# MBC3_multi_1-3.net
KiCad netlist of a schematic drawn in EAGLE
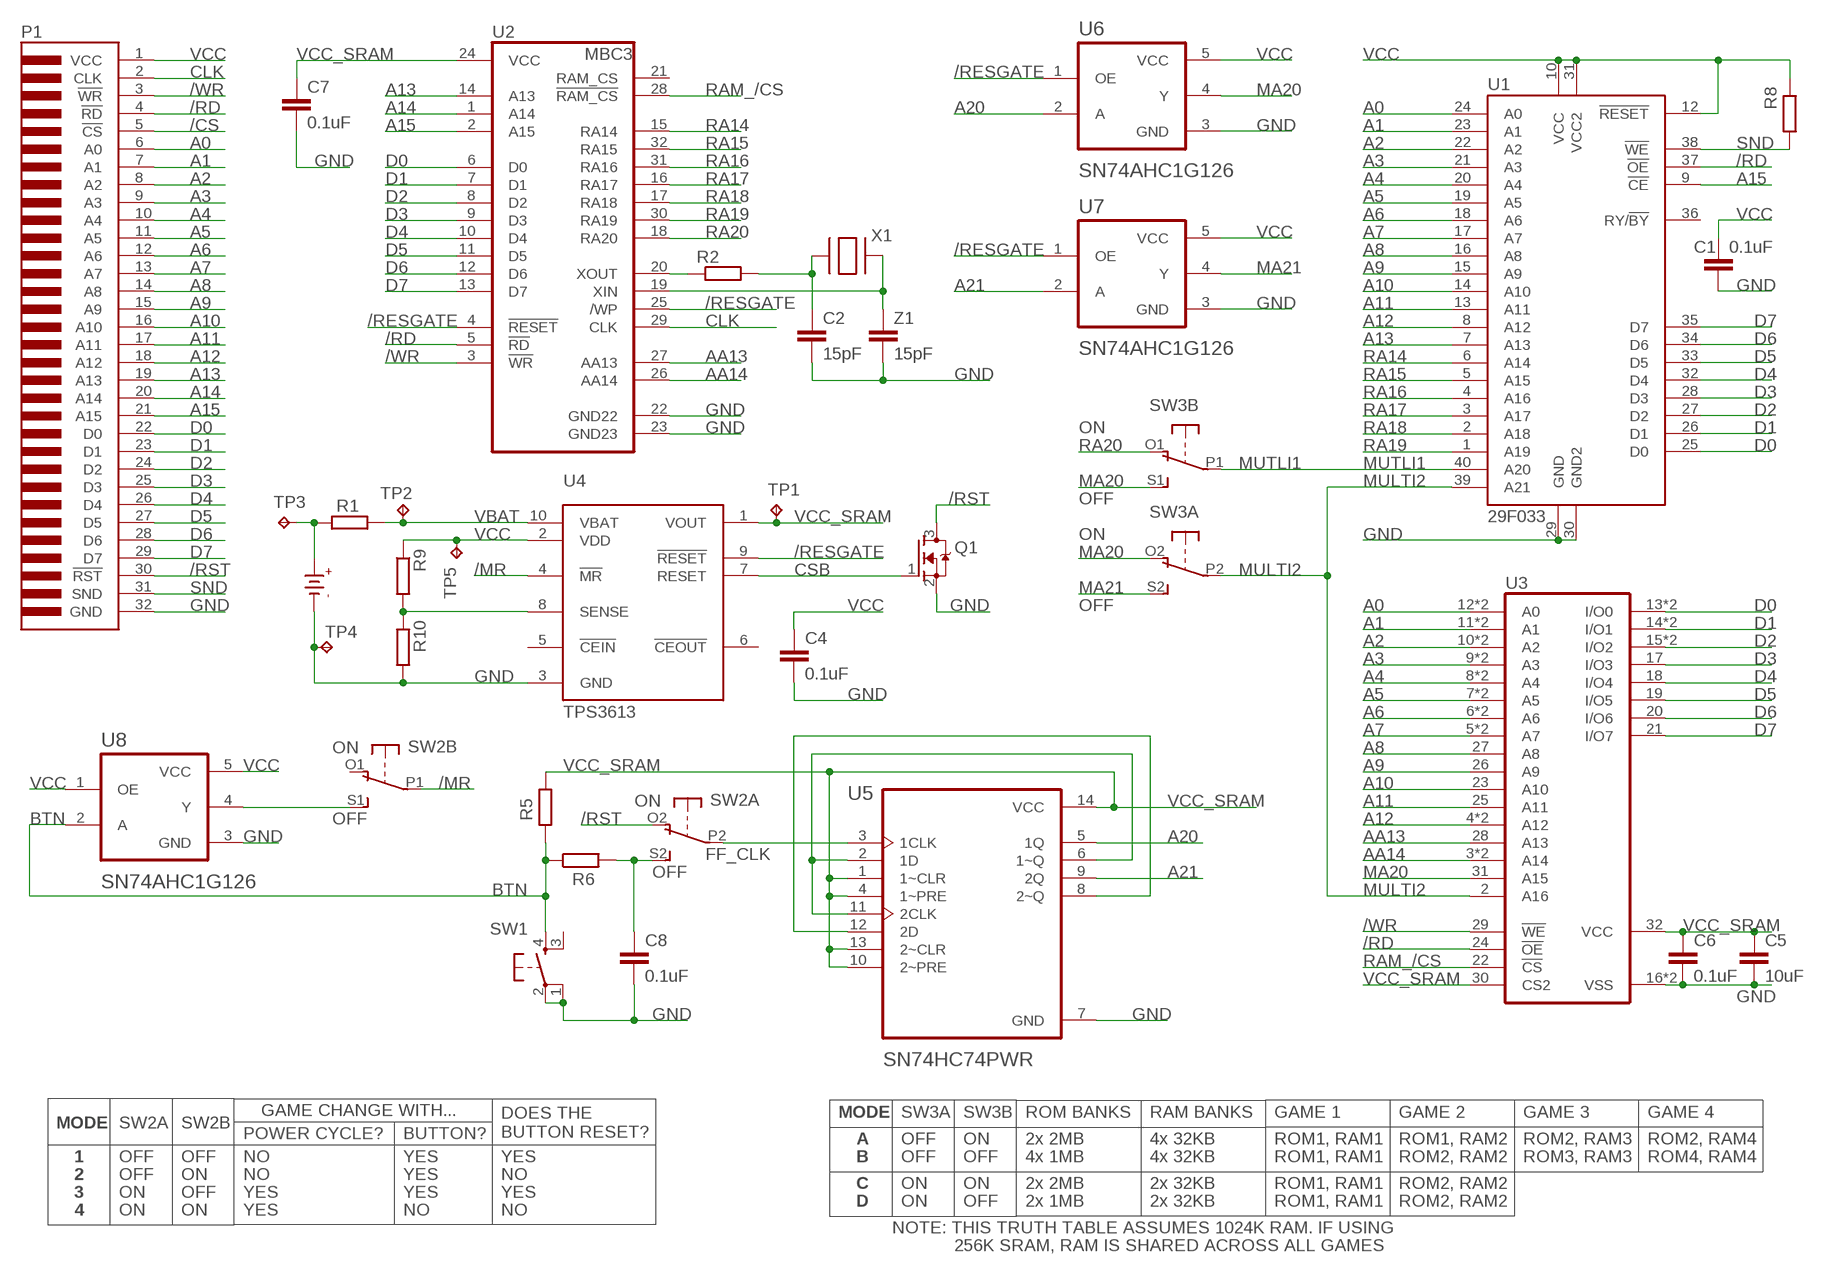
[diagram p0: schematic, sheet 1]

(export (version "E")
  (design (tool "Eeschema 10.0.6"))
  (components
    (comp (ref "C1")
      (value "0.1uF")
      (footprint "eagle-import:C0603")
      (libsource (lib "eagle-import") (part "C-EUC0603"))
    )
    (comp (ref "C2")
      (value "15pF")
      (footprint "eagle-import:C0603")
      (libsource (lib "eagle-import") (part "C-EUC0603"))
    )
    (comp (ref "C4")
      (value "0.1uF")
      (footprint "eagle-import:C0603")
      (libsource (lib "eagle-import") (part "C-EUC0603"))
    )
    (comp (ref "C5")
      (value "10uF")
      (footprint "eagle-import:C0603")
      (libsource (lib "eagle-import") (part "C-EUC0603"))
    )
    (comp (ref "C6")
      (value "0.1uF")
      (footprint "eagle-import:C0603")
      (libsource (lib "eagle-import") (part "C-EUC0603"))
    )
    (comp (ref "C7")
      (value "0.1uF")
      (footprint "eagle-import:C0603")
      (libsource (lib "eagle-import") (part "C-EUC0603"))
    )
    (comp (ref "C8")
      (value "0.1uF")
      (footprint "eagle-import:C0603")
      (libsource (lib "eagle-import") (part "C-EUC0603"))
    )
    (comp (ref "P1")
      (value "GBC_CARTTAB")
      (footprint "eagle-import:GBC_CART_TABBED")
      (libsource (lib "eagle-import") (part "GBC_CARTTAB"))
    )
    (comp (ref "Q1")
      (value "2N7002")
      (footprint "eagle-import:SOT23")
      (libsource (lib "eagle-import") (part "MOSFET-NREFLOW"))
    )
    (comp (ref "R1")
      (value "RR0603")
      (footprint "eagle-import:R0603")
      (libsource (lib "eagle-import") (part "RR0603"))
    )
    (comp (ref "R2")
      (value "RR0603")
      (footprint "eagle-import:R0603")
      (libsource (lib "eagle-import") (part "RR0603"))
    )
    (comp (ref "R5")
      (value "RR0603")
      (footprint "eagle-import:R0603")
      (libsource (lib "eagle-import") (part "RR0603"))
    )
    (comp (ref "R6")
      (value "RR0603")
      (footprint "eagle-import:R0603")
      (libsource (lib "eagle-import") (part "RR0603"))
    )
    (comp (ref "R8")
      (value "RR0603")
      (footprint "eagle-import:R0603")
      (libsource (lib "eagle-import") (part "RR0603"))
    )
    (comp (ref "R9")
      (value "RR0603")
      (footprint "eagle-import:R0603")
      (libsource (lib "eagle-import") (part "RR0603"))
    )
    (comp (ref "R10")
      (value "RR0603")
      (footprint "eagle-import:R0603")
      (libsource (lib "eagle-import") (part "RR0603"))
    )
    (comp (ref "SW1")
      (value "SPST_TACT-KMR2")
      (footprint "eagle-import:KMR2")
      (libsource (lib "eagle-import") (part "SPST_TACT-KMR2"))
    )
    (comp (ref "SW2")
      (value "SPDT-2S")
      (footprint "eagle-import:CAS-D20A")
      (libsource (lib "eagle-import") (part "SPDT-2S"))
    )
    (comp (ref "SW3")
      (value "SPDT-2S")
      (footprint "eagle-import:CAS-D20A")
      (libsource (lib "eagle-import") (part "SPDT-2S"))
    )
    (comp (ref "TP1")
      (value "TPB1,27")
      (footprint "eagle-import:B1,27")
      (libsource (lib "eagle-import") (part "TPB1,27"))
    )
    (comp (ref "TP2")
      (value "TPB1,27")
      (footprint "eagle-import:B1,27")
      (libsource (lib "eagle-import") (part "TPB1,27"))
    )
    (comp (ref "TP3")
      (value "TPB1,27")
      (footprint "eagle-import:B1,27")
      (libsource (lib "eagle-import") (part "TPB1,27"))
    )
    (comp (ref "TP4")
      (value "TPB1,27")
      (footprint "eagle-import:B1,27")
      (libsource (lib "eagle-import") (part "TPB1,27"))
    )
    (comp (ref "TP5")
      (value "TPB1,27")
      (footprint "eagle-import:B1,27")
      (libsource (lib "eagle-import") (part "TPB1,27"))
    )
    (comp (ref "U$7")
      (value "CR2025")
      (footprint "eagle-import:CR2025")
      (libsource (lib "eagle-import") (part "CR2025"))
    )
    (comp (ref "U1")
      (value "29F033")
      (footprint "eagle-import:TSOP-40")
      (libsource (lib "eagle-import") (part "29F033"))
    )
    (comp (ref "U2")
      (value "MBC3")
      (footprint "eagle-import:QFP-32")
      (libsource (lib "eagle-import") (part "MBC3"))
    )
    (comp (ref "U3")
      (value "1008_62256_SRAM")
      (footprint "eagle-import:SOP-32L")
      (libsource (lib "eagle-import") (part "1008_62256_SRAM"))
    )
    (comp (ref "U4")
      (value "TPS3613")
      (footprint "eagle-import:MSOP-10")
      (libsource (lib "eagle-import") (part "TPS3613"))
    )
    (comp (ref "U5")
      (value "SN74HC74PWR")
      (footprint "eagle-import:SOP65P640X120-14N")
      (fields (field (name "MF") "Texas Instruments"))
      (libsource (lib "eagle-import") (part "SN74HC74PWR"))
    )
    (comp (ref "U6")
      (value "SN74AHC1G126")
      (footprint "eagle-import:SC70")
      (libsource (lib "eagle-import") (part "SN74AHC1G126"))
    )
    (comp (ref "U7")
      (value "SN74AHC1G126")
      (footprint "eagle-import:SC70")
      (libsource (lib "eagle-import") (part "SN74AHC1G126"))
    )
    (comp (ref "U8")
      (value "SN74AHC1G126")
      (footprint "eagle-import:SC70")
      (libsource (lib "eagle-import") (part "SN74AHC1G126"))
    )
    (comp (ref "X1")
      (value "XTAL-3.2X1.5")
      (footprint "eagle-import:XTAL3215")
      (libsource (lib "eagle-import") (part "XTAL-3.2X1.5"))
    )
    (comp (ref "Z1")
      (value "15pF")
      (footprint "eagle-import:C0603")
      (libsource (lib "eagle-import") (part "C-EUC0603"))
    )
  )
  (nets
    (net (code "1") (name "/A0") (class "Default")
      (node (ref "P1") (pin "6") (pinfunction "A0_6") (pintype "output"))
      (node (ref "U1") (pin "24") (pinfunction "A0_24") (pintype "input"))
      (node (ref "U3") (pin "12") (pinfunction "A0_12") (pintype "input"))
      (node (ref "U3") (pin "L12") (pinfunction "A0_L12") (pintype "input"))
    )
    (net (code "2") (name "/A1") (class "Default")
      (node (ref "P1") (pin "7") (pinfunction "A1_7") (pintype "output"))
      (node (ref "U1") (pin "23") (pinfunction "A1_23") (pintype "input"))
      (node (ref "U3") (pin "11") (pinfunction "A1_11") (pintype "input"))
      (node (ref "U3") (pin "L11") (pinfunction "A1_L11") (pintype "input"))
    )
    (net (code "3") (name "/A2") (class "Default")
      (node (ref "P1") (pin "8") (pinfunction "A2_8") (pintype "output"))
      (node (ref "U1") (pin "22") (pinfunction "A2_22") (pintype "input"))
      (node (ref "U3") (pin "10") (pinfunction "A2_10") (pintype "input"))
      (node (ref "U3") (pin "L10") (pinfunction "A2_L10") (pintype "input"))
    )
    (net (code "4") (name "/A3") (class "Default")
      (node (ref "P1") (pin "9") (pinfunction "A3_9") (pintype "output"))
      (node (ref "U1") (pin "21") (pinfunction "A3_21") (pintype "input"))
      (node (ref "U3") (pin "9") (pinfunction "A3_9") (pintype "input"))
      (node (ref "U3") (pin "L9") (pinfunction "A3_L9") (pintype "input"))
    )
    (net (code "5") (name "/A4") (class "Default")
      (node (ref "P1") (pin "10") (pinfunction "A4_10") (pintype "output"))
      (node (ref "U1") (pin "20") (pinfunction "A4_20") (pintype "input"))
      (node (ref "U3") (pin "8") (pinfunction "A4_8") (pintype "input"))
      (node (ref "U3") (pin "L8") (pinfunction "A4_L8") (pintype "input"))
    )
    (net (code "6") (name "/A5") (class "Default")
      (node (ref "P1") (pin "11") (pinfunction "A5_11") (pintype "output"))
      (node (ref "U1") (pin "19") (pinfunction "A5_19") (pintype "input"))
      (node (ref "U3") (pin "7") (pinfunction "A5_7") (pintype "input"))
      (node (ref "U3") (pin "L7") (pinfunction "A5_L7") (pintype "input"))
    )
    (net (code "7") (name "/A6") (class "Default")
      (node (ref "P1") (pin "12") (pinfunction "A6_12") (pintype "output"))
      (node (ref "U1") (pin "18") (pinfunction "A6_18") (pintype "input"))
      (node (ref "U3") (pin "6") (pinfunction "A6_6") (pintype "input"))
      (node (ref "U3") (pin "L6") (pinfunction "A6_L6") (pintype "input"))
    )
    (net (code "8") (name "/A7") (class "Default")
      (node (ref "P1") (pin "13") (pinfunction "A7_13") (pintype "output"))
      (node (ref "U1") (pin "17") (pinfunction "A7_17") (pintype "input"))
      (node (ref "U3") (pin "5") (pinfunction "A7_5") (pintype "input"))
      (node (ref "U3") (pin "L5") (pinfunction "A7_L5") (pintype "input"))
    )
    (net (code "9") (name "/A8") (class "Default")
      (node (ref "P1") (pin "14") (pinfunction "A8_14") (pintype "output"))
      (node (ref "U1") (pin "16") (pinfunction "A8_16") (pintype "input"))
      (node (ref "U3") (pin "27") (pinfunction "A8_27") (pintype "input"))
    )
    (net (code "10") (name "/A9") (class "Default")
      (node (ref "P1") (pin "15") (pinfunction "A9_15") (pintype "output"))
      (node (ref "U1") (pin "15") (pinfunction "A9_15") (pintype "input"))
      (node (ref "U3") (pin "26") (pinfunction "A9_26") (pintype "input"))
    )
    (net (code "11") (name "/A10") (class "Default")
      (node (ref "P1") (pin "16") (pinfunction "A10_16") (pintype "output"))
      (node (ref "U1") (pin "14") (pinfunction "A10_14") (pintype "input"))
      (node (ref "U3") (pin "23") (pinfunction "A10_23") (pintype "input"))
    )
    (net (code "12") (name "/A11") (class "Default")
      (node (ref "P1") (pin "17") (pinfunction "A11_17") (pintype "output"))
      (node (ref "U1") (pin "13") (pinfunction "A11_13") (pintype "input"))
      (node (ref "U3") (pin "25") (pinfunction "A11_25") (pintype "input"))
    )
    (net (code "13") (name "/A12") (class "Default")
      (node (ref "P1") (pin "18") (pinfunction "A12_18") (pintype "output"))
      (node (ref "U1") (pin "8") (pinfunction "A12_8") (pintype "input"))
      (node (ref "U3") (pin "4") (pinfunction "A12_4") (pintype "input"))
      (node (ref "U3") (pin "L4") (pinfunction "A12_L4") (pintype "input"))
    )
    (net (code "14") (name "/A13") (class "Default")
      (node (ref "P1") (pin "19") (pinfunction "A13_19") (pintype "output"))
      (node (ref "U1") (pin "7") (pinfunction "A13_7") (pintype "input"))
      (node (ref "U2") (pin "14") (pinfunction "A13_14") (pintype "input"))
    )
    (net (code "15") (name "/A14") (class "Default")
      (node (ref "P1") (pin "20") (pinfunction "A14_20") (pintype "output"))
      (node (ref "U2") (pin "1") (pinfunction "A14_1") (pintype "input"))
    )
    (net (code "16") (name "/A15") (class "Default")
      (node (ref "P1") (pin "21") (pinfunction "A15_21") (pintype "output"))
      (node (ref "U1") (pin "9") (pinfunction "~{CE}_9") (pintype "input"))
      (node (ref "U2") (pin "2") (pinfunction "A15_2") (pintype "input"))
    )
    (net (code "17") (name "/A20") (class "Default")
      (node (ref "U5") (pin "5") (pinfunction "1Q_5") (pintype "output"))
      (node (ref "U6") (pin "2") (pinfunction "A_2") (pintype "input"))
    )
    (net (code "18") (name "/A21") (class "Default")
      (node (ref "U5") (pin "9") (pinfunction "2Q_9") (pintype "output"))
      (node (ref "U7") (pin "2") (pinfunction "A_2") (pintype "input"))
    )
    (net (code "19") (name "/AA13") (class "Default")
      (node (ref "U2") (pin "27") (pinfunction "AA13_27") (pintype "output"))
      (node (ref "U3") (pin "28") (pinfunction "A13_28") (pintype "input"))
    )
    (net (code "20") (name "/AA14") (class "Default")
      (node (ref "U2") (pin "26") (pinfunction "AA14_26") (pintype "output"))
      (node (ref "U3") (pin "3") (pinfunction "A14_3") (pintype "input"))
      (node (ref "U3") (pin "L3") (pinfunction "A14_L3") (pintype "input"))
    )
    (net (code "21") (name "/BTN") (class "Default")
      (node (ref "R5") (pin "2") (pinfunction "2_2") (pintype "passive"))
      (node (ref "R6") (pin "1") (pinfunction "1_1") (pintype "passive"))
      (node (ref "SW1") (pin "4") (pinfunction "S_4") (pintype "passive"))
      (node (ref "U8") (pin "2") (pinfunction "A_2") (pintype "input"))
    )
    (net (code "22") (name "/CLK") (class "Default")
      (node (ref "P1") (pin "2") (pinfunction "CLK_2") (pintype "output"))
      (node (ref "U2") (pin "29") (pinfunction "CLK_29") (pintype "output"))
    )
    (net (code "23") (name "/CSB") (class "Default")
      (node (ref "Q1") (pin "1") (pinfunction "G_1") (pintype "bidirectional"))
      (node (ref "U4") (pin "7") (pinfunction "RESET_7") (pintype "output"))
    )
    (net (code "24") (name "/D0") (class "Default")
      (node (ref "P1") (pin "22") (pinfunction "D0_22") (pintype "bidirectional"))
      (node (ref "U1") (pin "25") (pinfunction "D0_25") (pintype "bidirectional"))
      (node (ref "U2") (pin "6") (pinfunction "D0_6") (pintype "input"))
      (node (ref "U3") (pin "13") (pinfunction "I/O0_13") (pintype "bidirectional"))
      (node (ref "U3") (pin "L13") (pinfunction "I/O0_L13") (pintype "bidirectional"))
    )
    (net (code "25") (name "/D1") (class "Default")
      (node (ref "P1") (pin "23") (pinfunction "D1_23") (pintype "bidirectional"))
      (node (ref "U1") (pin "26") (pinfunction "D1_26") (pintype "bidirectional"))
      (node (ref "U2") (pin "7") (pinfunction "D1_7") (pintype "input"))
      (node (ref "U3") (pin "14") (pinfunction "I/O1_14") (pintype "bidirectional"))
      (node (ref "U3") (pin "L14") (pinfunction "I/O1_L14") (pintype "bidirectional"))
    )
    (net (code "26") (name "/D2") (class "Default")
      (node (ref "P1") (pin "24") (pinfunction "D2_24") (pintype "bidirectional"))
      (node (ref "U1") (pin "27") (pinfunction "D2_27") (pintype "bidirectional"))
      (node (ref "U2") (pin "8") (pinfunction "D2_8") (pintype "input"))
      (node (ref "U3") (pin "15") (pinfunction "I/O2_15") (pintype "bidirectional"))
      (node (ref "U3") (pin "L15") (pinfunction "I/O2_L15") (pintype "bidirectional"))
    )
    (net (code "27") (name "/D3") (class "Default")
      (node (ref "P1") (pin "25") (pinfunction "D3_25") (pintype "bidirectional"))
      (node (ref "U1") (pin "28") (pinfunction "D3_28") (pintype "bidirectional"))
      (node (ref "U2") (pin "9") (pinfunction "D3_9") (pintype "input"))
      (node (ref "U3") (pin "17") (pinfunction "I/O3_17") (pintype "bidirectional"))
    )
    (net (code "28") (name "/D4") (class "Default")
      (node (ref "P1") (pin "26") (pinfunction "D4_26") (pintype "bidirectional"))
      (node (ref "U1") (pin "32") (pinfunction "D4_32") (pintype "bidirectional"))
      (node (ref "U2") (pin "10") (pinfunction "D4_10") (pintype "input"))
      (node (ref "U3") (pin "18") (pinfunction "I/O4_18") (pintype "bidirectional"))
    )
    (net (code "29") (name "/D5") (class "Default")
      (node (ref "P1") (pin "27") (pinfunction "D5_27") (pintype "bidirectional"))
      (node (ref "U1") (pin "33") (pinfunction "D5_33") (pintype "bidirectional"))
      (node (ref "U2") (pin "11") (pinfunction "D5_11") (pintype "input"))
      (node (ref "U3") (pin "19") (pinfunction "I/O5_19") (pintype "bidirectional"))
    )
    (net (code "30") (name "/D6") (class "Default")
      (node (ref "P1") (pin "28") (pinfunction "D6_28") (pintype "bidirectional"))
      (node (ref "U1") (pin "34") (pinfunction "D6_34") (pintype "bidirectional"))
      (node (ref "U2") (pin "12") (pinfunction "D6_12") (pintype "input"))
      (node (ref "U3") (pin "20") (pinfunction "I/O6_20") (pintype "bidirectional"))
    )
    (net (code "31") (name "/D7") (class "Default")
      (node (ref "P1") (pin "29") (pinfunction "D7_29") (pintype "bidirectional"))
      (node (ref "U1") (pin "35") (pinfunction "D7_35") (pintype "bidirectional"))
      (node (ref "U2") (pin "13") (pinfunction "D7_13") (pintype "input"))
      (node (ref "U3") (pin "21") (pinfunction "I/O7_21") (pintype "bidirectional"))
    )
    (net (code "32") (name "/FF_CLK") (class "Default")
      (node (ref "SW2") (pin "P2") (pinfunction "P_P2") (pintype "passive"))
      (node (ref "U5") (pin "3") (pinfunction "1CLK_3") (pintype "input"))
    )
    (net (code "33") (name "/GND") (class "Default")
      (node (ref "C1") (pin "2") (pinfunction "2_2") (pintype "passive"))
      (node (ref "C2") (pin "2") (pinfunction "2_2") (pintype "passive"))
      (node (ref "C4") (pin "2") (pinfunction "2_2") (pintype "passive"))
      (node (ref "C5") (pin "2") (pinfunction "2_2") (pintype "passive"))
      (node (ref "C6") (pin "2") (pinfunction "2_2") (pintype "passive"))
      (node (ref "C7") (pin "2") (pinfunction "2_2") (pintype "passive"))
      (node (ref "C8") (pin "2") (pinfunction "2_2") (pintype "passive"))
      (node (ref "P1") (pin "32") (pinfunction "GND_32") (pintype "power_in"))
      (node (ref "Q1") (pin "2") (pinfunction "S_2") (pintype "bidirectional"))
      (node (ref "R10") (pin "2") (pinfunction "2_2") (pintype "passive"))
      (node (ref "SW1") (pin "1") (pinfunction "P1_1") (pintype "passive"))
      (node (ref "SW1") (pin "2") (pinfunction "P_2") (pintype "passive"))
      (node (ref "TP4") (pin "TP") (pinfunction "TP_TP") (pintype "input"))
      (node (ref "U$7") (pin "-") (pinfunction "-_-") (pintype "power_in"))
      (node (ref "U1") (pin "29") (pinfunction "GND_29") (pintype "power_in"))
      (node (ref "U1") (pin "30") (pinfunction "GND2_30") (pintype "power_in"))
      (node (ref "U2") (pin "22") (pinfunction "GND22_22") (pintype "power_in"))
      (node (ref "U2") (pin "23") (pinfunction "GND23_23") (pintype "power_in"))
      (node (ref "U3") (pin "16") (pinfunction "VSS_16") (pintype "power_in"))
      (node (ref "U3") (pin "L16") (pinfunction "VSS_L16") (pintype "power_in"))
      (node (ref "U4") (pin "3") (pinfunction "GND_3") (pintype "power_in"))
      (node (ref "U5") (pin "7") (pinfunction "GND_7") (pintype "power_in"))
      (node (ref "U6") (pin "3") (pinfunction "GND_3") (pintype "power_in"))
      (node (ref "U7") (pin "3") (pinfunction "GND_3") (pintype "power_in"))
      (node (ref "U8") (pin "3") (pinfunction "GND_3") (pintype "power_in"))
      (node (ref "Z1") (pin "2") (pinfunction "2_2") (pintype "passive"))
    )
    (net (code "34") (name "/MA20") (class "Default")
      (node (ref "SW3") (pin "O2") (pinfunction "O_O2") (pintype "passive"))
      (node (ref "SW3") (pin "S1") (pinfunction "S_S1") (pintype "passive"))
      (node (ref "U3") (pin "31") (pinfunction "A15_31") (pintype "input"))
      (node (ref "U6") (pin "4") (pinfunction "Y_4") (pintype "output"))
    )
    (net (code "35") (name "/MA21") (class "Default")
      (node (ref "SW3") (pin "S2") (pinfunction "S_S2") (pintype "passive"))
      (node (ref "U7") (pin "4") (pinfunction "Y_4") (pintype "output"))
    )
    (net (code "36") (name "/MULTI2") (class "Default")
      (node (ref "SW3") (pin "P2") (pinfunction "P_P2") (pintype "passive"))
      (node (ref "U1") (pin "39") (pinfunction "A21_39") (pintype "input"))
      (node (ref "U3") (pin "2") (pinfunction "A16_2") (pintype "input"))
    )
    (net (code "37") (name "/MUTLI1") (class "Default")
      (node (ref "SW3") (pin "P1") (pinfunction "P_P1") (pintype "passive"))
      (node (ref "U1") (pin "40") (pinfunction "A20_40") (pintype "input"))
    )
    (net (code "38") (name "/RA14") (class "Default")
      (node (ref "U1") (pin "6") (pinfunction "A14_6") (pintype "input"))
      (node (ref "U2") (pin "15") (pinfunction "RA14_15") (pintype "output"))
    )
    (net (code "39") (name "/RA15") (class "Default")
      (node (ref "U1") (pin "5") (pinfunction "A15_5") (pintype "input"))
      (node (ref "U2") (pin "32") (pinfunction "RA15_32") (pintype "output"))
    )
    (net (code "40") (name "/RA16") (class "Default")
      (node (ref "U1") (pin "4") (pinfunction "A16_4") (pintype "input"))
      (node (ref "U2") (pin "31") (pinfunction "RA16_31") (pintype "output"))
    )
    (net (code "41") (name "/RA17") (class "Default")
      (node (ref "U1") (pin "3") (pinfunction "A17_3") (pintype "input"))
      (node (ref "U2") (pin "16") (pinfunction "RA17_16") (pintype "output"))
    )
    (net (code "42") (name "/RA18") (class "Default")
      (node (ref "U1") (pin "2") (pinfunction "A18_2") (pintype "input"))
      (node (ref "U2") (pin "17") (pinfunction "RA18_17") (pintype "output"))
    )
    (net (code "43") (name "/RA19") (class "Default")
      (node (ref "U1") (pin "1") (pinfunction "A19_1") (pintype "input"))
      (node (ref "U2") (pin "30") (pinfunction "RA19_30") (pintype "output"))
    )
    (net (code "44") (name "/RA20") (class "Default")
      (node (ref "SW3") (pin "O1") (pinfunction "O_O1") (pintype "passive"))
      (node (ref "U2") (pin "18") (pinfunction "RA20_18") (pintype "output"))
    )
    (net (code "45") (name "/RAM_{slash}CS") (class "Default")
      (node (ref "U2") (pin "28") (pinfunction "~{RAM_CS}_28") (pintype "output"))
      (node (ref "U3") (pin "22") (pinfunction "~{CS}_22") (pintype "input"))
    )
    (net (code "46") (name "/SND") (class "Default")
      (node (ref "P1") (pin "31") (pinfunction "SND_31") (pintype "bidirectional"))
      (node (ref "R8") (pin "2") (pinfunction "2_2") (pintype "passive"))
      (node (ref "U1") (pin "38") (pinfunction "~{WE}_38") (pintype "input"))
    )
    (net (code "47") (name "/VBAT") (class "Default")
      (node (ref "R1") (pin "1") (pinfunction "1_1") (pintype "passive"))
      (node (ref "TP2") (pin "TP") (pinfunction "TP_TP") (pintype "input"))
      (node (ref "U4") (pin "10") (pinfunction "VBAT_10") (pintype "power_in"))
    )
    (net (code "48") (name "/VCC") (class "Default")
      (node (ref "C1") (pin "1") (pinfunction "1_1") (pintype "passive"))
      (node (ref "C4") (pin "1") (pinfunction "1_1") (pintype "passive"))
      (node (ref "P1") (pin "1") (pinfunction "VCC_1") (pintype "power_in"))
      (node (ref "R8") (pin "1") (pinfunction "1_1") (pintype "passive"))
      (node (ref "R9") (pin "1") (pinfunction "1_1") (pintype "passive"))
      (node (ref "TP5") (pin "TP") (pinfunction "TP_TP") (pintype "input"))
      (node (ref "U1") (pin "10") (pinfunction "VCC_10") (pintype "power_in"))
      (node (ref "U1") (pin "12") (pinfunction "~{RESET}_12") (pintype "input"))
      (node (ref "U1") (pin "31") (pinfunction "VCC2_31") (pintype "power_in"))
      (node (ref "U4") (pin "2") (pinfunction "VDD_2") (pintype "power_in"))
      (node (ref "U6") (pin "5") (pinfunction "VCC_5") (pintype "power_in"))
      (node (ref "U7") (pin "5") (pinfunction "VCC_5") (pintype "power_in"))
      (node (ref "U8") (pin "1") (pinfunction "OE_1") (pintype "input"))
      (node (ref "U8") (pin "5") (pinfunction "VCC_5") (pintype "power_in"))
    )
    (net (code "49") (name "/VCC_SRAM") (class "Default")
      (node (ref "C5") (pin "1") (pinfunction "1_1") (pintype "passive"))
      (node (ref "C6") (pin "1") (pinfunction "1_1") (pintype "passive"))
      (node (ref "C7") (pin "1") (pinfunction "1_1") (pintype "passive"))
      (node (ref "R5") (pin "1") (pinfunction "1_1") (pintype "passive"))
      (node (ref "TP1") (pin "TP") (pinfunction "TP_TP") (pintype "input"))
      (node (ref "U2") (pin "24") (pinfunction "VCC_24") (pintype "power_in"))
      (node (ref "U3") (pin "30") (pinfunction "CS2_30") (pintype "input"))
      (node (ref "U3") (pin "32") (pinfunction "VCC_32") (pintype "power_in"))
      (node (ref "U4") (pin "1") (pinfunction "VOUT_1") (pintype "power_in"))
      (node (ref "U5") (pin "1") (pinfunction "1~{CLR}_1") (pintype "input"))
      (node (ref "U5") (pin "10") (pinfunction "2~{PRE}_10") (pintype "input"))
      (node (ref "U5") (pin "13") (pinfunction "2~{CLR}_13") (pintype "input"))
      (node (ref "U5") (pin "14") (pinfunction "VCC_14") (pintype "power_in"))
      (node (ref "U5") (pin "4") (pinfunction "1~{PRE}_4") (pintype "input"))
    )
    (net (code "50") (name "/{slash}CS") (class "Default")
      (node (ref "P1") (pin "5") (pinfunction "~{CS}_5") (pintype "output"))
    )
    (net (code "51") (name "/{slash}MR") (class "Default")
      (node (ref "SW2") (pin "P1") (pinfunction "P_P1") (pintype "passive"))
      (node (ref "U4") (pin "4") (pinfunction "~{MR}_4") (pintype "input"))
    )
    (net (code "52") (name "/{slash}RD") (class "Default")
      (node (ref "P1") (pin "4") (pinfunction "~{RD}_4") (pintype "output"))
      (node (ref "U1") (pin "37") (pinfunction "~{OE}_37") (pintype "input"))
      (node (ref "U2") (pin "5") (pinfunction "~{RD}_5") (pintype "input"))
      (node (ref "U3") (pin "24") (pinfunction "~{OE}_24") (pintype "input"))
    )
    (net (code "53") (name "/{slash}RESGATE") (class "Default")
      (node (ref "U2") (pin "25") (pinfunction "/WP_25") (pintype "output"))
      (node (ref "U2") (pin "4") (pinfunction "~{RESET}_4") (pintype "input"))
      (node (ref "U4") (pin "9") (pinfunction "~{RESET}_9") (pintype "output"))
      (node (ref "U6") (pin "1") (pinfunction "OE_1") (pintype "input"))
      (node (ref "U7") (pin "1") (pinfunction "OE_1") (pintype "input"))
    )
    (net (code "54") (name "/{slash}RST") (class "Default")
      (node (ref "P1") (pin "30") (pinfunction "~{RST}_30") (pintype "bidirectional"))
      (node (ref "Q1") (pin "3") (pinfunction "D_3") (pintype "bidirectional"))
      (node (ref "SW2") (pin "O2") (pinfunction "O_O2") (pintype "passive"))
    )
    (net (code "55") (name "/{slash}WR") (class "Default")
      (node (ref "P1") (pin "3") (pinfunction "~{WR}_3") (pintype "output"))
      (node (ref "U2") (pin "3") (pinfunction "~{WR}_3") (pintype "input"))
      (node (ref "U3") (pin "29") (pinfunction "~{WE}_29") (pintype "input"))
    )
    (net (code "56") (name "Net-(C2-Pad1)") (class "Default")
      (node (ref "C2") (pin "1") (pinfunction "1_1") (pintype "passive"))
      (node (ref "R2") (pin "2") (pinfunction "2_2") (pintype "passive"))
      (node (ref "X1") (pin "P$2") (pinfunction "P$2_P$2") (pintype "bidirectional"))
    )
    (net (code "57") (name "Net-(R1-Pad2)") (class "Default")
      (node (ref "R1") (pin "2") (pinfunction "2_2") (pintype "passive"))
      (node (ref "TP3") (pin "TP") (pinfunction "TP_TP") (pintype "input"))
      (node (ref "U$7") (pin "+") (pinfunction "+_+") (pintype "power_in"))
    )
    (net (code "58") (name "Net-(SW2A-S)") (class "Default")
      (node (ref "SW2") (pin "S1") (pinfunction "S_S1") (pintype "passive"))
      (node (ref "U8") (pin "4") (pinfunction "Y_4") (pintype "output"))
    )
    (net (code "59") (name "Net-(SW2B-S)") (class "Default")
      (node (ref "C8") (pin "1") (pinfunction "1_1") (pintype "passive"))
      (node (ref "R6") (pin "2") (pinfunction "2_2") (pintype "passive"))
      (node (ref "SW2") (pin "S2") (pinfunction "S_S2") (pintype "passive"))
    )
    (net (code "60") (name "Net-(U2-XIN)") (class "Default")
      (node (ref "U2") (pin "19") (pinfunction "XIN_19") (pintype "input"))
      (node (ref "X1") (pin "P$1") (pinfunction "P$1_P$1") (pintype "bidirectional"))
      (node (ref "Z1") (pin "1") (pinfunction "1_1") (pintype "passive"))
    )
    (net (code "61") (name "Net-(U2-XOUT)") (class "Default")
      (node (ref "R2") (pin "1") (pinfunction "1_1") (pintype "passive"))
      (node (ref "U2") (pin "20") (pinfunction "XOUT_20") (pintype "output"))
    )
    (net (code "62") (name "Net-(U4-SENSE)") (class "Default")
      (node (ref "R10") (pin "1") (pinfunction "1_1") (pintype "passive"))
      (node (ref "R9") (pin "2") (pinfunction "2_2") (pintype "passive"))
      (node (ref "U4") (pin "8") (pinfunction "SENSE_8") (pintype "input"))
    )
    (net (code "63") (name "Net-(U5-1D)") (class "Default")
      (node (ref "U5") (pin "11") (pinfunction "2CLK_11") (pintype "input"))
      (node (ref "U5") (pin "2") (pinfunction "1D_2") (pintype "input"))
      (node (ref "U5") (pin "6") (pinfunction "1~{Q}_6") (pintype "output"))
    )
    (net (code "64") (name "Net-(U5-2D)") (class "Default")
      (node (ref "U5") (pin "12") (pinfunction "2D_12") (pintype "input"))
      (node (ref "U5") (pin "8") (pinfunction "2~{Q}_8") (pintype "output"))
    )
    (net (code "65") (name "unconnected-(SW1-S1-Pad3)") (class "Default")
      (node (ref "SW1") (pin "3") (pinfunction "S1_3") (pintype "passive"))
    )
    (net (code "66") (name "unconnected-(SW2A-O-PadO1)") (class "Default")
      (node (ref "SW2") (pin "O1") (pinfunction "O_O1") (pintype "passive"))
    )
    (net (code "67") (name "unconnected-(U1-RY{slash}~{BY}-Pad36)") (class "Default")
      (node (ref "U1") (pin "36") (pinfunction "RY/~{BY}_36") (pintype "output"))
    )
    (net (code "68") (name "unconnected-(U2-RAM_CS-Pad21)") (class "Default")
      (node (ref "U2") (pin "21") (pinfunction "RAM_CS_21") (pintype "output"))
    )
    (net (code "69") (name "unconnected-(U4-~{CEIN}-Pad5)") (class "Default")
      (node (ref "U4") (pin "5") (pinfunction "~{CEIN}_5") (pintype "input"))
    )
    (net (code "70") (name "unconnected-(U4-~{CEOUT}-Pad6)") (class "Default")
      (node (ref "U4") (pin "6") (pinfunction "~{CEOUT}_6") (pintype "output"))
    )
  )
)
